# Sheet1_-_Copy.net
KiCad netlist of a schematic drawn in Altium Designer
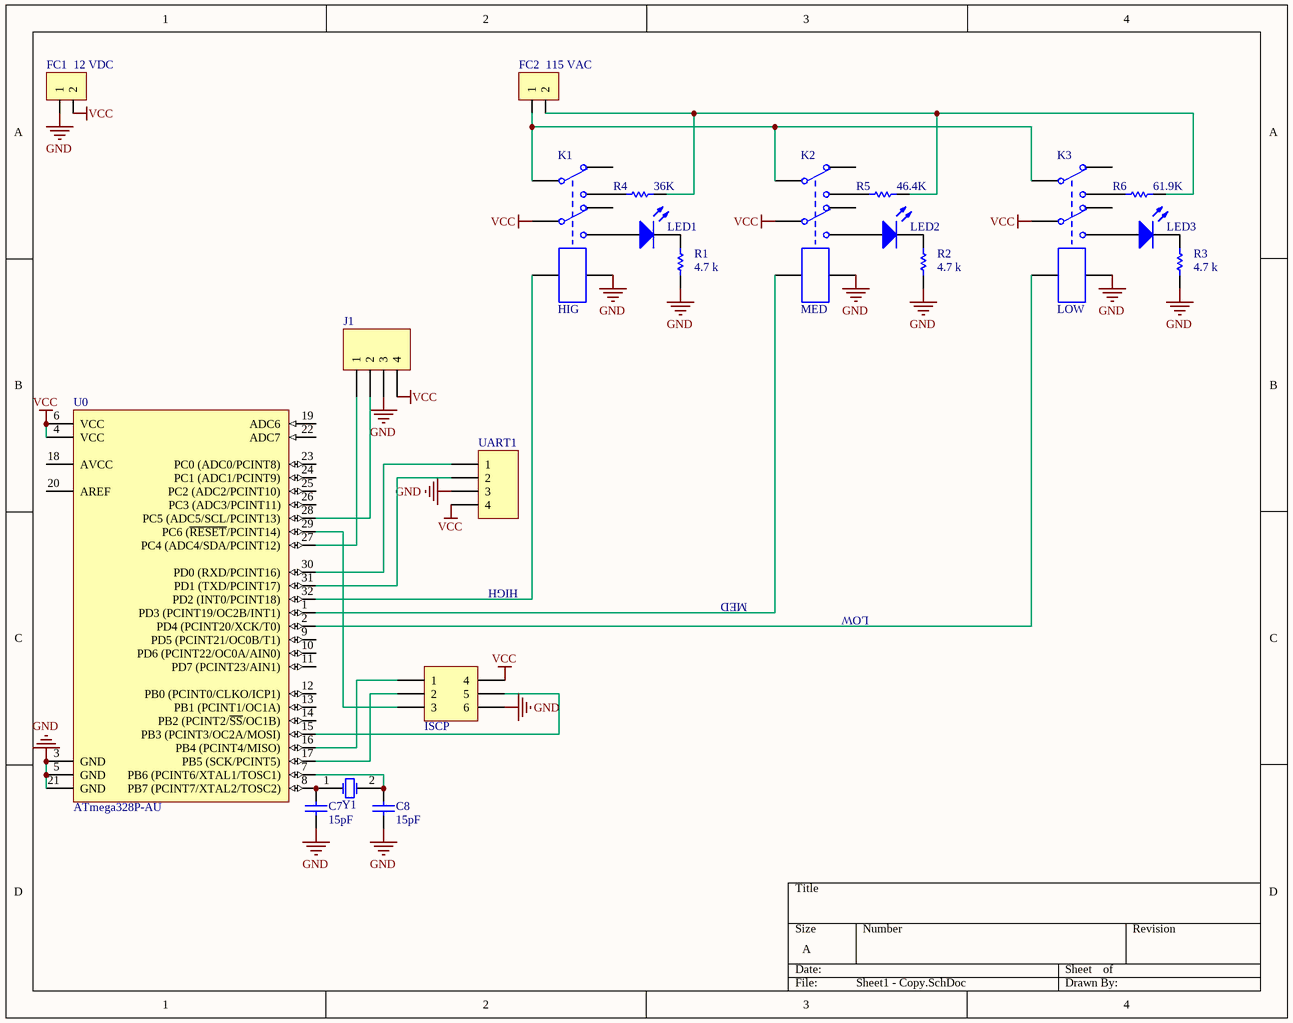
[diagram p0: Sheet1 - Copy.SchDoc]

(export (version "E")
  (design (tool "Eeschema 10.0.6"))
  (components
    (comp (ref "C7")
      (value "15pF")
      (footprint "Cap1206_throu")
      (description "Capacitor")
      (fields (field (name "Comment") "Cap") (field (name "PUBLISHER") "Altium Limited"))
      (libsource (lib "Miscellaneous Devices") (part "Cap"))
    )
    (comp (ref "C8")
      (value "15pF")
      (footprint "Cap1206_throu")
      (description "Capacitor")
      (fields (field (name "Comment") "Cap") (field (name "PUBLISHER") "Altium Limited"))
      (libsource (lib "Miscellaneous Devices") (part "Cap"))
    )
    (comp (ref "FC1")
      (value "12 VDC")
      (footprint "CONNECTOR")
      (description "CONNECTOR")
      (libsource (lib "Schlib1") (part "CONNECTOR"))
    )
    (comp (ref "FC2")
      (value "115 VAC")
      (footprint "CONNECTOR")
      (description "CONNECTOR")
      (libsource (lib "Schlib1") (part "CONNECTOR"))
    )
    (comp (ref "J1")
      (value "Header 4")
      (footprint "HDR1X4")
      (description "Header, 4-Pin")
      (fields (field (name "PUBLISHER") "Altium Limited"))
      (libsource (lib "Miscellaneous Connectors") (part "Header 4"))
    )
    (comp (ref "K1")
      (value "HIG")
      (footprint "RELAY")
      (description "Dual-Pole Dual-Throw Relay")
      (fields (field (name "PUBLISHER") "Altium Limited"))
      (libsource (lib "Miscellaneous Devices") (part "Relay-DPDT"))
    )
    (comp (ref "K2")
      (value "MED")
      (footprint "RELAY")
      (description "Dual-Pole Dual-Throw Relay")
      (fields (field (name "PUBLISHER") "Altium Limited"))
      (libsource (lib "Miscellaneous Devices") (part "Relay-DPDT"))
    )
    (comp (ref "K3")
      (value "LOW")
      (footprint "RELAY")
      (description "Dual-Pole Dual-Throw Relay")
      (fields (field (name "PUBLISHER") "Altium Limited"))
      (libsource (lib "Miscellaneous Devices") (part "Relay-DPDT"))
    )
    (comp (ref "LED1")
      (value "~")
      (footprint "LED")
      (description "Typical INFRARED GaAs LED")
      (fields (field (name "PUBLISHER") "Altium Limited"))
      (libsource (lib "Miscellaneous Devices") (part "LED0"))
    )
    (comp (ref "LED2")
      (value "~")
      (footprint "LED")
      (description "Typical INFRARED GaAs LED")
      (fields (field (name "PUBLISHER") "Altium Limited"))
      (libsource (lib "Miscellaneous Devices") (part "LED0"))
    )
    (comp (ref "LED3")
      (value "~")
      (footprint "LED")
      (description "Typical INFRARED GaAs LED")
      (fields (field (name "PUBLISHER") "Altium Limited"))
      (libsource (lib "Miscellaneous Devices") (part "LED0"))
    )
    (comp (ref "P11")
      (value "ISCP")
      (footprint "HDR2X3_CEN")
      (description "Header, 3-Pin, Dual row")
      (fields (field (name "PUBLISHER") "Altium Limited"))
      (libsource (lib "Miscellaneous Connectors") (part "Header 3X2A"))
    )
    (comp (ref "R1")
      (value "4.7 k")
      (footprint "Cap1206_throu")
      (description "Resistor")
      (fields (field (name "Comment") "Res1") (field (name "PUBLISHER") "Altium Limited"))
      (libsource (lib "Miscellaneous Devices") (part "Res1"))
    )
    (comp (ref "R2")
      (value "4.7 k")
      (footprint "Cap1206_throu")
      (description "Resistor")
      (fields (field (name "Comment") "Res1") (field (name "PUBLISHER") "Altium Limited"))
      (libsource (lib "Miscellaneous Devices") (part "Res1"))
    )
    (comp (ref "R3")
      (value "4.7 k")
      (footprint "Cap1206_throu")
      (description "Resistor")
      (fields (field (name "Comment") "Res1") (field (name "PUBLISHER") "Altium Limited"))
      (libsource (lib "Miscellaneous Devices") (part "Res1"))
    )
    (comp (ref "R4")
      (value "36K")
      (footprint "AXIAL-0.3")
      (description "Resistor")
      (fields (field (name "Comment") "Res1") (field (name "PUBLISHER") "Altium Limited"))
      (libsource (lib "Miscellaneous Devices") (part "Res1"))
    )
    (comp (ref "R5")
      (value "46.4K")
      (footprint "AXIAL-0.3")
      (description "Resistor")
      (fields (field (name "Comment") "Res1") (field (name "PUBLISHER") "Altium Limited"))
      (libsource (lib "Miscellaneous Devices") (part "Res1"))
    )
    (comp (ref "R6")
      (value "61.9K")
      (footprint "AXIAL-0.3")
      (description "Resistor")
      (fields (field (name "Comment") "Res1") (field (name "PUBLISHER") "Altium Limited"))
      (libsource (lib "Miscellaneous Devices") (part "Res1"))
    )
    (comp (ref "U0")
      (value "ATmega328P-AU")
      (footprint "32A_N")
      (fields (field (name "PUBLISHER") "Altium Limited"))
      (libsource (lib "Atmel Microcontroller 8-Bit megaAVR") (part "ATmega328P-AU"))
    )
    (comp (ref "UART1")
      (value "Header 4")
      (footprint "HDR1X4")
      (description "Header, 4-Pin")
      (fields (field (name "PUBLISHER") "Altium Limited"))
      (libsource (lib "") (part "Header 4_1"))
    )
    (comp (ref "Y1")
      (value "XTAL")
      (footprint "CRYSTAL")
      (description "Crystal Oscillator")
      (fields (field (name "PUBLISHER") "Altium Limited"))
      (libsource (lib "Miscellaneous Devices") (part "XTAL"))
    )
  )
  (nets
    (net (code "1") (name "GND") (class "Default")
      (node (ref "C7") (pin "1") (pinfunction "1_1") (pintype "passive"))
      (node (ref "C8") (pin "1") (pinfunction "1_1") (pintype "passive"))
      (node (ref "FC1") (pin "1") (pinfunction "1_1") (pintype "passive"))
      (node (ref "J1") (pin "3") (pinfunction "3_3") (pintype "passive"))
      (node (ref "K1") (pin "8") (pinfunction "8_8") (pintype "passive"))
      (node (ref "K2") (pin "8") (pinfunction "8_8") (pintype "passive"))
      (node (ref "K3") (pin "8") (pinfunction "8_8") (pintype "passive"))
      (node (ref "P11") (pin "6") (pinfunction "6_6") (pintype "passive"))
      (node (ref "R1") (pin "1") (pinfunction "1_1") (pintype "passive"))
      (node (ref "R2") (pin "1") (pinfunction "1_1") (pintype "passive"))
      (node (ref "R3") (pin "1") (pinfunction "1_1") (pintype "passive"))
      (node (ref "U0") (pin "21") (pinfunction "GND_21") (pintype "power_in"))
      (node (ref "U0") (pin "3") (pinfunction "GND_3") (pintype "power_in"))
      (node (ref "U0") (pin "5") (pinfunction "GND_5") (pintype "power_in"))
      (node (ref "UART1") (pin "3") (pinfunction "3_3") (pintype "passive"))
    )
    (net (code "2") (name "Net-(FC2-Pad1)") (class "Default")
      (node (ref "FC2") (pin "1") (pinfunction "1_1") (pintype "passive"))
      (node (ref "K1") (pin "1") (pinfunction "1_1") (pintype "passive"))
      (node (ref "K2") (pin "1") (pinfunction "1_1") (pintype "passive"))
      (node (ref "K3") (pin "1") (pinfunction "1_1") (pintype "passive"))
    )
    (net (code "3") (name "Net-(FC2-Pad2)") (class "Default")
      (node (ref "FC2") (pin "2") (pinfunction "2_2") (pintype "passive"))
      (node (ref "R4") (pin "2") (pinfunction "2_2") (pintype "passive"))
      (node (ref "R5") (pin "2") (pinfunction "2_2") (pintype "passive"))
      (node (ref "R6") (pin "2") (pinfunction "2_2") (pintype "passive"))
    )
    (net (code "4") (name "Net-(K1-Pad3)") (class "Default")
      (node (ref "K1") (pin "3") (pinfunction "3_3") (pintype "passive"))
      (node (ref "R4") (pin "1") (pinfunction "1_1") (pintype "passive"))
    )
    (net (code "5") (name "Net-(K2-Pad3)") (class "Default")
      (node (ref "K2") (pin "3") (pinfunction "3_3") (pintype "passive"))
      (node (ref "R5") (pin "1") (pinfunction "1_1") (pintype "passive"))
    )
    (net (code "6") (name "Net-(K3-Pad3)") (class "Default")
      (node (ref "K3") (pin "3") (pinfunction "3_3") (pintype "passive"))
      (node (ref "R6") (pin "1") (pinfunction "1_1") (pintype "passive"))
    )
    (net (code "7") (name "Net-(LED1-A)") (class "Default")
      (node (ref "K1") (pin "6") (pinfunction "6_6") (pintype "passive"))
      (node (ref "LED1") (pin "1") (pinfunction "A_1") (pintype "passive"))
    )
    (net (code "8") (name "Net-(LED1-K)") (class "Default")
      (node (ref "LED1") (pin "2") (pinfunction "K_2") (pintype "passive"))
      (node (ref "R1") (pin "2") (pinfunction "2_2") (pintype "passive"))
    )
    (net (code "9") (name "Net-(LED2-A)") (class "Default")
      (node (ref "K2") (pin "6") (pinfunction "6_6") (pintype "passive"))
      (node (ref "LED2") (pin "1") (pinfunction "A_1") (pintype "passive"))
    )
    (net (code "10") (name "Net-(LED2-K)") (class "Default")
      (node (ref "LED2") (pin "2") (pinfunction "K_2") (pintype "passive"))
      (node (ref "R2") (pin "2") (pinfunction "2_2") (pintype "passive"))
    )
    (net (code "11") (name "Net-(LED3-A)") (class "Default")
      (node (ref "K3") (pin "6") (pinfunction "6_6") (pintype "passive"))
      (node (ref "LED3") (pin "1") (pinfunction "A_1") (pintype "passive"))
    )
    (net (code "12") (name "Net-(LED3-K)") (class "Default")
      (node (ref "LED3") (pin "2") (pinfunction "K_2") (pintype "passive"))
      (node (ref "R3") (pin "2") (pinfunction "2_2") (pintype "passive"))
    )
    (net (code "13") (name "Net-(U0-PB3_(PCINT3{slash}OC2A{slash}MOSI))") (class "Default")
      (node (ref "P11") (pin "5") (pinfunction "5_5") (pintype "passive"))
      (node (ref "U0") (pin "15") (pinfunction "PB3_(PCINT3/OC2A/MOSI)_15") (pintype "bidirectional"))
    )
    (net (code "14") (name "Net-(U0-PB4_(PCINT4{slash}MISO))") (class "Default")
      (node (ref "P11") (pin "1") (pinfunction "1_1") (pintype "passive"))
      (node (ref "U0") (pin "16") (pinfunction "PB4_(PCINT4/MISO)_16") (pintype "bidirectional"))
    )
    (net (code "15") (name "Net-(U0-PB5_(SCK{slash}PCINT5))") (class "Default")
      (node (ref "P11") (pin "2") (pinfunction "2_2") (pintype "passive"))
      (node (ref "U0") (pin "17") (pinfunction "PB5_(SCK/PCINT5)_17") (pintype "bidirectional"))
    )
    (net (code "16") (name "Net-(U0-PB6_(PCINT6{slash}XTAL1{slash}TOSC1))") (class "Default")
      (node (ref "C8") (pin "2") (pinfunction "2_2") (pintype "passive"))
      (node (ref "U0") (pin "7") (pinfunction "PB6_(PCINT6/XTAL1/TOSC1)_7") (pintype "bidirectional"))
      (node (ref "Y1") (pin "2") (pinfunction "OSC2_2") (pintype "passive"))
    )
    (net (code "17") (name "Net-(U0-PB7_(PCINT7{slash}XTAL2{slash}TOSC2))") (class "Default")
      (node (ref "C7") (pin "2") (pinfunction "2_2") (pintype "passive"))
      (node (ref "U0") (pin "8") (pinfunction "PB7_(PCINT7/XTAL2/TOSC2)_8") (pintype "bidirectional"))
      (node (ref "Y1") (pin "1") (pinfunction "OSC1_1") (pintype "passive"))
    )
    (net (code "18") (name "Net-(U0-PC4_(ADC4{slash}SDA{slash}PCINT12))") (class "Default")
      (node (ref "J1") (pin "1") (pinfunction "1_1") (pintype "passive"))
      (node (ref "U0") (pin "27") (pinfunction "PC4_(ADC4/SDA/PCINT12)_27") (pintype "bidirectional"))
    )
    (net (code "19") (name "Net-(U0-PC5_(ADC5{slash}SCL{slash}PCINT13))") (class "Default")
      (node (ref "J1") (pin "2") (pinfunction "2_2") (pintype "passive"))
      (node (ref "U0") (pin "28") (pinfunction "PC5_(ADC5/SCL/PCINT13)_28") (pintype "bidirectional"))
    )
    (net (code "20") (name "Net-(U0-PC6_(~{RESET}{slash}PCINT14))") (class "Default")
      (node (ref "P11") (pin "3") (pinfunction "3_3") (pintype "passive"))
      (node (ref "U0") (pin "29") (pinfunction "PC6_(~{RESET}/PCINT14)_29") (pintype "bidirectional"))
    )
    (net (code "21") (name "Net-(U0-PD0_(RXD{slash}PCINT16))") (class "Default")
      (node (ref "U0") (pin "30") (pinfunction "PD0_(RXD/PCINT16)_30") (pintype "bidirectional"))
      (node (ref "UART1") (pin "1") (pinfunction "1_1") (pintype "passive"))
    )
    (net (code "22") (name "Net-(U0-PD1_(TXD{slash}PCINT17))") (class "Default")
      (node (ref "U0") (pin "31") (pinfunction "PD1_(TXD/PCINT17)_31") (pintype "bidirectional"))
      (node (ref "UART1") (pin "2") (pinfunction "2_2") (pintype "passive"))
    )
    (net (code "23") (name "Net-(U0-PD2_(INT0{slash}PCINT18))") (class "Default")
      (node (ref "K1") (pin "7") (pinfunction "7_7") (pintype "passive"))
      (node (ref "U0") (pin "32") (pinfunction "PD2_(INT0/PCINT18)_32") (pintype "bidirectional"))
    )
    (net (code "24") (name "Net-(U0-PD3_(PCINT19{slash}OC2B{slash}INT1))") (class "Default")
      (node (ref "K2") (pin "7") (pinfunction "7_7") (pintype "passive"))
      (node (ref "U0") (pin "1") (pinfunction "PD3_(PCINT19/OC2B/INT1)_1") (pintype "bidirectional"))
    )
    (net (code "25") (name "Net-(U0-PD4_(PCINT20{slash}XCK{slash}T0))") (class "Default")
      (node (ref "K3") (pin "7") (pinfunction "7_7") (pintype "passive"))
      (node (ref "U0") (pin "2") (pinfunction "PD4_(PCINT20/XCK/T0)_2") (pintype "bidirectional"))
    )
    (net (code "26") (name "VCC") (class "Default")
      (node (ref "FC1") (pin "2") (pinfunction "2_2") (pintype "passive"))
      (node (ref "J1") (pin "4") (pinfunction "4_4") (pintype "passive"))
      (node (ref "K1") (pin "4") (pinfunction "4_4") (pintype "passive"))
      (node (ref "K2") (pin "4") (pinfunction "4_4") (pintype "passive"))
      (node (ref "K3") (pin "4") (pinfunction "4_4") (pintype "passive"))
      (node (ref "P11") (pin "4") (pinfunction "4_4") (pintype "passive"))
      (node (ref "U0") (pin "4") (pinfunction "VCC_4") (pintype "power_in"))
      (node (ref "U0") (pin "6") (pinfunction "VCC_6") (pintype "power_in"))
      (node (ref "UART1") (pin "4") (pinfunction "4_4") (pintype "passive"))
    )
    (net (code "27") (name "unconnected-(K1-Pad2)") (class "Default")
      (node (ref "K1") (pin "2") (pinfunction "2_2") (pintype "passive"))
    )
    (net (code "28") (name "unconnected-(K1-Pad5)") (class "Default")
      (node (ref "K1") (pin "5") (pinfunction "5_5") (pintype "passive"))
    )
    (net (code "29") (name "unconnected-(K2-Pad2)") (class "Default")
      (node (ref "K2") (pin "2") (pinfunction "2_2") (pintype "passive"))
    )
    (net (code "30") (name "unconnected-(K2-Pad5)") (class "Default")
      (node (ref "K2") (pin "5") (pinfunction "5_5") (pintype "passive"))
    )
    (net (code "31") (name "unconnected-(K3-Pad2)") (class "Default")
      (node (ref "K3") (pin "2") (pinfunction "2_2") (pintype "passive"))
    )
    (net (code "32") (name "unconnected-(K3-Pad5)") (class "Default")
      (node (ref "K3") (pin "5") (pinfunction "5_5") (pintype "passive"))
    )
    (net (code "33") (name "unconnected-(U0-ADC6-Pad19)") (class "Default")
      (node (ref "U0") (pin "19") (pinfunction "ADC6_19") (pintype "input"))
    )
    (net (code "34") (name "unconnected-(U0-ADC7-Pad22)") (class "Default")
      (node (ref "U0") (pin "22") (pinfunction "ADC7_22") (pintype "input"))
    )
    (net (code "35") (name "unconnected-(U0-AREF-Pad20)") (class "Default")
      (node (ref "U0") (pin "20") (pinfunction "AREF_20") (pintype "passive"))
    )
    (net (code "36") (name "unconnected-(U0-AVCC-Pad18)") (class "Default")
      (node (ref "U0") (pin "18") (pinfunction "AVCC_18") (pintype "power_in"))
    )
    (net (code "37") (name "unconnected-(U0-PB0_(PCINT0{slash}CLKO{slash}ICP1)-Pad12)") (class "Default")
      (node (ref "U0") (pin "12") (pinfunction "PB0_(PCINT0/CLKO/ICP1)_12") (pintype "bidirectional"))
    )
    (net (code "38") (name "unconnected-(U0-PB1_(PCINT1{slash}OC1A)-Pad13)") (class "Default")
      (node (ref "U0") (pin "13") (pinfunction "PB1_(PCINT1/OC1A)_13") (pintype "bidirectional"))
    )
    (net (code "39") (name "unconnected-(U0-PB2_(PCINT2{slash}~{SS}{slash}OC1B)-Pad14)") (class "Default")
      (node (ref "U0") (pin "14") (pinfunction "PB2_(PCINT2/~{SS}/OC1B)_14") (pintype "bidirectional"))
    )
    (net (code "40") (name "unconnected-(U0-PC0_(ADC0{slash}PCINT8)-Pad23)") (class "Default")
      (node (ref "U0") (pin "23") (pinfunction "PC0_(ADC0/PCINT8)_23") (pintype "bidirectional"))
    )
    (net (code "41") (name "unconnected-(U0-PC1_(ADC1{slash}PCINT9)-Pad24)") (class "Default")
      (node (ref "U0") (pin "24") (pinfunction "PC1_(ADC1/PCINT9)_24") (pintype "bidirectional"))
    )
    (net (code "42") (name "unconnected-(U0-PC2_(ADC2{slash}PCINT10)-Pad25)") (class "Default")
      (node (ref "U0") (pin "25") (pinfunction "PC2_(ADC2/PCINT10)_25") (pintype "bidirectional"))
    )
    (net (code "43") (name "unconnected-(U0-PC3_(ADC3{slash}PCINT11)-Pad26)") (class "Default")
      (node (ref "U0") (pin "26") (pinfunction "PC3_(ADC3/PCINT11)_26") (pintype "bidirectional"))
    )
    (net (code "44") (name "unconnected-(U0-PD5_(PCINT21{slash}OC0B{slash}T1)-Pad9)") (class "Default")
      (node (ref "U0") (pin "9") (pinfunction "PD5_(PCINT21/OC0B/T1)_9") (pintype "bidirectional"))
    )
    (net (code "45") (name "unconnected-(U0-PD6_(PCINT22{slash}OC0A{slash}AIN0)-Pad10)") (class "Default")
      (node (ref "U0") (pin "10") (pinfunction "PD6_(PCINT22/OC0A/AIN0)_10") (pintype "bidirectional"))
    )
    (net (code "46") (name "unconnected-(U0-PD7_(PCINT23{slash}AIN1)-Pad11)") (class "Default")
      (node (ref "U0") (pin "11") (pinfunction "PD7_(PCINT23/AIN1)_11") (pintype "bidirectional"))
    )
  )
)
